# arm_v1.net
KiCad netlist of a schematic drawn in Altium Designer
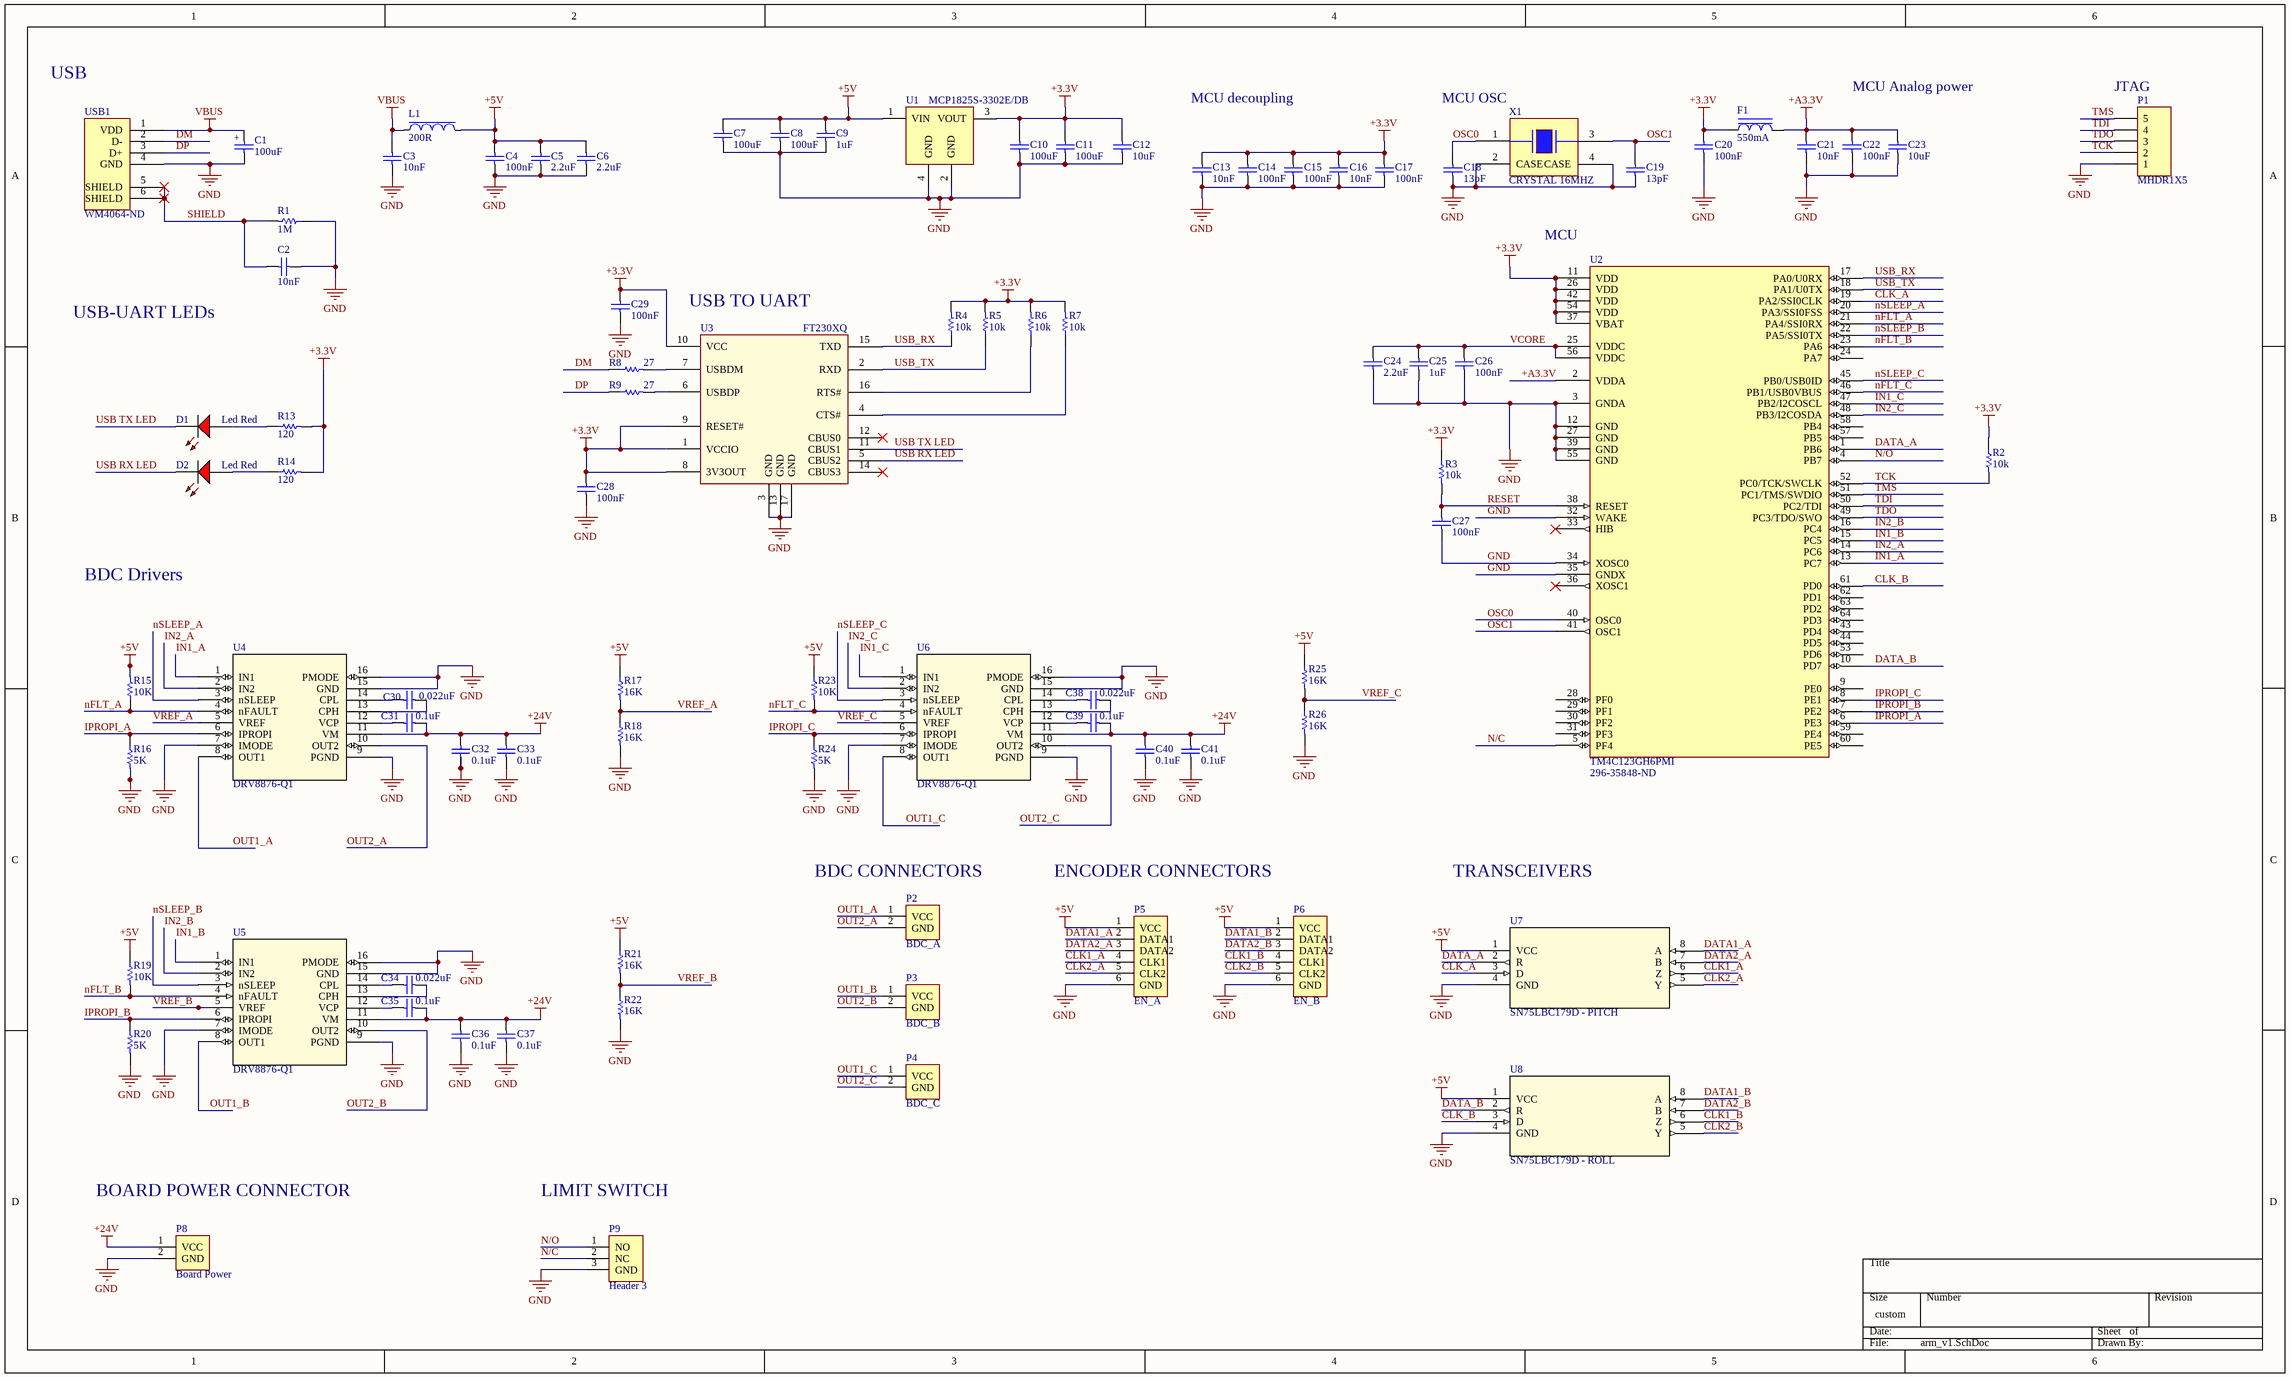
[diagram p0: arm_v1.SchDoc]

(export (version "E")
  (design (tool "Eeschema 10.0.6"))
  (components
    (comp (ref "C1")
      (value "100uF")
      (footprint "CapAlu6.3mmx12.5mm")
      (description "Capacitor 35v 100uF 6.3mm")
      (fields
        (field (name "MANUFACTURER") "Nichicon")
        (field (name "MANUFACTURER PART NUMBER") "UHV1V101MED")
      )
      (libsource (lib "Capacitors") (part "100uF_35v_6.3x12.5"))
    )
    (comp (ref "C2")
      (value "10nF")
      (footprint "CAP_1206")
      (description "CAP CER 10000PF 500V X7R 1206")
      (fields
        (field (name "MANUFACTURER") "Samsung Electro-Mechanics America, Inc")
        (field (name "MANUFACTURER PART NUMBER") "CL31B103KGFNNNE")
      )
      (libsource (lib "Capacitors") (part "10nF_500V_1206"))
    )
    (comp (ref "C3")
      (value "10nF")
      (footprint "CAP_0402_M")
      (description "CAP CER 10000PF 50V 10% X7R 0402")
      (fields
        (field (name "MANUFACTURER") "Kemet")
        (field (name "MANUFACTURER PART NUMBER") "C0402C103K5RACTU")
      )
      (libsource (lib "Capacitors") (part "10nF_50V_0402"))
    )
    (comp (ref "C4")
      (value "100nF")
      (footprint "CAP_0402_M")
      (description "CAP CER 100NF 50V 20% X5R 0402")
      (fields
        (field (name "MANUFACTURER") "TDK Corporation")
        (field (name "MANUFACTURER PART NUMBER") "C1005X5R1H104M050BB")
      )
      (libsource (lib "Capacitors") (part "100nF_50V_0402"))
    )
    (comp (ref "C5")
      (value "2.2uF")
      (footprint "CAP_0402_M")
      (description "CAP CER 2.2UF 10V 20% X5R 0402")
      (fields
        (field (name "MANUFACTURER") "Taiyo Yuden")
        (field (name "MANUFACTURER PART NUMBER") "LMK105BJ225MV-F")
      )
      (libsource (lib "Capacitors") (part "2.2uF_10V_0402"))
    )
    (comp (ref "C6")
      (value "2.2uF")
      (footprint "CAP_0402_M")
      (description "CAP CER 2.2UF 10V 20% X5R 0402")
      (fields
        (field (name "MANUFACTURER") "Taiyo Yuden")
        (field (name "MANUFACTURER PART NUMBER") "LMK105BJ225MV-F")
      )
      (libsource (lib "Capacitors") (part "2.2uF_10V_0402"))
    )
    (comp (ref "C7")
      (value "100uF")
      (footprint "CAP_1206")
      (description "CAP CER 100UF 6.3V X5R 1206")
      (fields
        (field (name "MANUFACTURER") "Murata Electronics North America")
        (field (name "MANUFACTURER PART NUMBER") "GRM31CR60J107ME39L")
      )
      (libsource (lib "Capacitors") (part "100uF_6.3v_1206_X5R"))
    )
    (comp (ref "C8")
      (value "100uF")
      (footprint "CAP_1206")
      (description "CAP CER 100UF 6.3V X5R 1206")
      (fields
        (field (name "MANUFACTURER") "Murata Electronics North America")
        (field (name "MANUFACTURER PART NUMBER") "GRM31CR60J107ME39L")
      )
      (libsource (lib "Capacitors") (part "100uF_6.3v_1206_X5R"))
    )
    (comp (ref "C9")
      (value "1uF")
      (footprint "CAP_0402_M")
      (description "CAP CER 1UF 25V 10% X5R 0402")
      (fields
        (field (name "MANUFACTURER") "TDK Corporation")
        (field (name "MANUFACTURER PART NUMBER") "C1005X5R1E105K050BC")
      )
      (libsource (lib "Capacitors") (part "1uF_25V_0402"))
    )
    (comp (ref "C10")
      (value "100uF")
      (footprint "CAP_1206")
      (description "CAP CER 100UF 6.3V X5R 1206")
      (fields
        (field (name "MANUFACTURER") "Murata Electronics North America")
        (field (name "MANUFACTURER PART NUMBER") "GRM31CR60J107ME39L")
      )
      (libsource (lib "Capacitors") (part "100uF_6.3v_1206_X5R"))
    )
    (comp (ref "C11")
      (value "100uF")
      (footprint "CAP_1206")
      (description "CAP CER 100UF 6.3V X5R 1206")
      (fields
        (field (name "MANUFACTURER") "Murata Electronics North America")
        (field (name "MANUFACTURER PART NUMBER") "GRM31CR60J107ME39L")
      )
      (libsource (lib "Capacitors") (part "100uF_6.3v_1206_X5R"))
    )
    (comp (ref "C12")
      (value "10uF")
      (footprint "CAP_0603")
      (description "CAP CER 10UF 10V 20% X5R 0603")
      (fields
        (field (name "MANUFACTURER") "Taiyo Yuden")
        (field (name "MANUFACTURER PART NUMBER") "LMK107BBJ106MAHT")
      )
      (libsource (lib "Capacitors") (part "10uF_10V_0603"))
    )
    (comp (ref "C13")
      (value "10nF")
      (footprint "CAP_0402_M")
      (description "CAP CER 10000PF 50V 10% X7R 0402")
      (fields
        (field (name "MANUFACTURER") "Kemet")
        (field (name "MANUFACTURER PART NUMBER") "C0402C103K5RACTU")
      )
      (libsource (lib "Capacitors") (part "10nF_50V_0402"))
    )
    (comp (ref "C14")
      (value "100nF")
      (footprint "CAP_0402_M")
      (description "CAP CER 100NF 50V 20% X5R 0402")
      (fields
        (field (name "MANUFACTURER") "TDK Corporation")
        (field (name "MANUFACTURER PART NUMBER") "C1005X5R1H104M050BB")
      )
      (libsource (lib "Capacitors") (part "100nF_50V_0402"))
    )
    (comp (ref "C15")
      (value "100nF")
      (footprint "CAP_0402_M")
      (description "CAP CER 100NF 50V 20% X5R 0402")
      (fields
        (field (name "MANUFACTURER") "TDK Corporation")
        (field (name "MANUFACTURER PART NUMBER") "C1005X5R1H104M050BB")
      )
      (libsource (lib "Capacitors") (part "100nF_50V_0402"))
    )
    (comp (ref "C16")
      (value "10nF")
      (footprint "CAP_0402_M")
      (description "CAP CER 10000PF 50V 10% X7R 0402")
      (fields
        (field (name "MANUFACTURER") "Kemet")
        (field (name "MANUFACTURER PART NUMBER") "C0402C103K5RACTU")
      )
      (libsource (lib "Capacitors") (part "10nF_50V_0402"))
    )
    (comp (ref "C17")
      (value "100nF")
      (footprint "CAP_0402_M")
      (description "CAP CER 100NF 50V 20% X5R 0402")
      (fields
        (field (name "MANUFACTURER") "TDK Corporation")
        (field (name "MANUFACTURER PART NUMBER") "C1005X5R1H104M050BB")
      )
      (libsource (lib "Capacitors") (part "100nF_50V_0402"))
    )
    (comp (ref "C18")
      (value "13pF")
      (footprint "CAP_0402_M")
      (description "CAP CER 13PF 50V 5% NP0 0402")
      (fields
        (field (name "MANUFACTURER") "Samsung Electro-Mechanics America, Inc")
        (field (name "MANUFACTURER PART NUMBER") "CL05C130JB5NNNC")
      )
      (libsource (lib "Capacitors") (part "13pF_50V_0402"))
    )
    (comp (ref "C19")
      (value "13pF")
      (footprint "CAP_0402_M")
      (description "CAP CER 13PF 50V 5% NP0 0402")
      (fields
        (field (name "MANUFACTURER") "Samsung Electro-Mechanics America, Inc")
        (field (name "MANUFACTURER PART NUMBER") "CL05C130JB5NNNC")
      )
      (libsource (lib "Capacitors") (part "13pF_50V_0402"))
    )
    (comp (ref "C20")
      (value "100nF")
      (footprint "CAP_0402_M")
      (description "CAP CER 100NF 50V 20% X5R 0402")
      (fields
        (field (name "MANUFACTURER") "TDK Corporation")
        (field (name "MANUFACTURER PART NUMBER") "C1005X5R1H104M050BB")
      )
      (libsource (lib "Capacitors") (part "100nF_50V_0402"))
    )
    (comp (ref "C21")
      (value "10nF")
      (footprint "CAP_0402_M")
      (description "CAP CER 10000PF 50V 10% X7R 0402")
      (fields
        (field (name "MANUFACTURER") "Kemet")
        (field (name "MANUFACTURER PART NUMBER") "C0402C103K5RACTU")
      )
      (libsource (lib "Capacitors") (part "10nF_50V_0402"))
    )
    (comp (ref "C22")
      (value "100nF")
      (footprint "CAP_0402_M")
      (description "CAP CER 100NF 50V 20% X5R 0402")
      (fields
        (field (name "MANUFACTURER") "TDK Corporation")
        (field (name "MANUFACTURER PART NUMBER") "C1005X5R1H104M050BB")
      )
      (libsource (lib "Capacitors") (part "100nF_50V_0402"))
    )
    (comp (ref "C23")
      (value "10uF")
      (footprint "CAP_0603")
      (description "CAP CER 10UF 10V 20% X5R 0603")
      (fields
        (field (name "MANUFACTURER") "Taiyo Yuden")
        (field (name "MANUFACTURER PART NUMBER") "LMK107BBJ106MAHT")
      )
      (libsource (lib "Capacitors") (part "10uF_10V_0603"))
    )
    (comp (ref "C24")
      (value "2.2uF")
      (footprint "CAP_0603")
      (description "CAP CER 2.2UF 35V 10% X5R 0603")
      (fields
        (field (name "MANUFACTURER") "Murata Electronics North America")
        (field (name "MANUFACTURER PART NUMBER") "GRM188R6YA225KA12D")
      )
      (libsource (lib "Capacitors") (part "2.2uF_35V_0603"))
    )
    (comp (ref "C25")
      (value "1uF")
      (footprint "CAP_0402_M")
      (description "CAP CER 1UF 25V 10% X5R 0402")
      (fields
        (field (name "MANUFACTURER") "TDK Corporation")
        (field (name "MANUFACTURER PART NUMBER") "C1005X5R1E105K050BC")
      )
      (libsource (lib "Capacitors") (part "1uF_25V_0402"))
    )
    (comp (ref "C26")
      (value "100nF")
      (footprint "CAP_0402_M")
      (description "CAP CER 100NF 50V 20% X5R 0402")
      (fields
        (field (name "MANUFACTURER") "TDK Corporation")
        (field (name "MANUFACTURER PART NUMBER") "C1005X5R1H104M050BB")
      )
      (libsource (lib "Capacitors") (part "100nF_50V_0402"))
    )
    (comp (ref "C27")
      (value "100nF")
      (footprint "CAP_0402_M")
      (description "CAP CER 100NF 50V 20% X5R 0402")
      (fields
        (field (name "MANUFACTURER") "TDK Corporation")
        (field (name "MANUFACTURER PART NUMBER") "C1005X5R1H104M050BB")
      )
      (libsource (lib "Capacitors") (part "100nF_50V_0402"))
    )
    (comp (ref "C28")
      (value "100nF")
      (footprint "CAP_0402_M")
      (description "CAP CER 100NF 50V 20% X5R 0402")
      (fields
        (field (name "MANUFACTURER") "TDK Corporation")
        (field (name "MANUFACTURER PART NUMBER") "C1005X5R1H104M050BB")
      )
      (libsource (lib "Capacitors") (part "100nF_50V_0402"))
    )
    (comp (ref "C29")
      (value "100nF")
      (footprint "CAP_0402_M")
      (description "CAP CER 100NF 50V 20% X5R 0402")
      (fields
        (field (name "MANUFACTURER") "TDK Corporation")
        (field (name "MANUFACTURER PART NUMBER") "C1005X5R1H104M050BB")
      )
      (libsource (lib "Capacitors") (part "100nF_50V_0402"))
    )
    (comp (ref "C30")
      (value "0.022uF")
      (footprint "CAP_0402_M")
      (description "CAP CER 100NF 50V 20% X5R 0402")
      (fields
        (field (name "MANUFACTURER") "TDK Corporation")
        (field (name "MANUFACTURER PART NUMBER") "C1005X5R1H104M050BB")
      )
      (libsource (lib "Capacitors") (part "100nF_50V_0402"))
    )
    (comp (ref "C31")
      (value "0.1uF")
      (footprint "CAP_0402_M")
      (description "CAP CER 100NF 50V 20% X5R 0402")
      (fields
        (field (name "MANUFACTURER") "TDK Corporation")
        (field (name "MANUFACTURER PART NUMBER") "C1005X5R1H104M050BB")
      )
      (libsource (lib "Capacitors") (part "100nF_50V_0402"))
    )
    (comp (ref "C32")
      (value "0.1uF")
      (footprint "CAP_0402_M")
      (description "CAP CER 100NF 50V 20% X5R 0402")
      (fields
        (field (name "MANUFACTURER") "TDK Corporation")
        (field (name "MANUFACTURER PART NUMBER") "C1005X5R1H104M050BB")
      )
      (libsource (lib "Capacitors") (part "100nF_50V_0402"))
    )
    (comp (ref "C33")
      (value "0.1uF")
      (footprint "CAP_0402_M")
      (description "CAP CER 100NF 50V 20% X5R 0402")
      (fields
        (field (name "MANUFACTURER") "TDK Corporation")
        (field (name "MANUFACTURER PART NUMBER") "C1005X5R1H104M050BB")
      )
      (libsource (lib "Capacitors") (part "100nF_50V_0402"))
    )
    (comp (ref "C34")
      (value "0.022uF")
      (footprint "CAP_0402_M")
      (description "CAP CER 100NF 50V 20% X5R 0402")
      (fields
        (field (name "MANUFACTURER") "TDK Corporation")
        (field (name "MANUFACTURER PART NUMBER") "C1005X5R1H104M050BB")
      )
      (libsource (lib "Capacitors") (part "100nF_50V_0402"))
    )
    (comp (ref "C35")
      (value "0.1uF")
      (footprint "CAP_0402_M")
      (description "CAP CER 100NF 50V 20% X5R 0402")
      (fields
        (field (name "MANUFACTURER") "TDK Corporation")
        (field (name "MANUFACTURER PART NUMBER") "C1005X5R1H104M050BB")
      )
      (libsource (lib "Capacitors") (part "100nF_50V_0402"))
    )
    (comp (ref "C36")
      (value "0.1uF")
      (footprint "CAP_0402_M")
      (description "CAP CER 100NF 50V 20% X5R 0402")
      (fields
        (field (name "MANUFACTURER") "TDK Corporation")
        (field (name "MANUFACTURER PART NUMBER") "C1005X5R1H104M050BB")
      )
      (libsource (lib "Capacitors") (part "100nF_50V_0402"))
    )
    (comp (ref "C37")
      (value "0.1uF")
      (footprint "CAP_0402_M")
      (description "CAP CER 100NF 50V 20% X5R 0402")
      (fields
        (field (name "MANUFACTURER") "TDK Corporation")
        (field (name "MANUFACTURER PART NUMBER") "C1005X5R1H104M050BB")
      )
      (libsource (lib "Capacitors") (part "100nF_50V_0402"))
    )
    (comp (ref "C38")
      (value "0.022uF")
      (footprint "CAP_0402_M")
      (description "CAP CER 100NF 50V 20% X5R 0402")
      (fields
        (field (name "MANUFACTURER") "TDK Corporation")
        (field (name "MANUFACTURER PART NUMBER") "C1005X5R1H104M050BB")
      )
      (libsource (lib "Capacitors") (part "100nF_50V_0402"))
    )
    (comp (ref "C39")
      (value "0.1uF")
      (footprint "CAP_0402_M")
      (description "CAP CER 100NF 50V 20% X5R 0402")
      (fields
        (field (name "MANUFACTURER") "TDK Corporation")
        (field (name "MANUFACTURER PART NUMBER") "C1005X5R1H104M050BB")
      )
      (libsource (lib "Capacitors") (part "100nF_50V_0402"))
    )
    (comp (ref "C40")
      (value "0.1uF")
      (footprint "CAP_0402_M")
      (description "CAP CER 100NF 50V 20% X5R 0402")
      (fields
        (field (name "MANUFACTURER") "TDK Corporation")
        (field (name "MANUFACTURER PART NUMBER") "C1005X5R1H104M050BB")
      )
      (libsource (lib "Capacitors") (part "100nF_50V_0402"))
    )
    (comp (ref "C41")
      (value "0.1uF")
      (footprint "CAP_0402_M")
      (description "CAP CER 100NF 50V 20% X5R 0402")
      (fields
        (field (name "MANUFACTURER") "TDK Corporation")
        (field (name "MANUFACTURER PART NUMBER") "C1005X5R1H104M050BB")
      )
      (libsource (lib "Capacitors") (part "100nF_50V_0402"))
    )
    (comp (ref "D1")
      (value "Led Red")
      (footprint "TOPLED 0805")
      (description "LED TOPLED 630NM SUP RED CLR SMD")
      (fields
        (field (name "MANUFACTURER") "OSRAM Opto Semiconductors Inc")
        (field (name "MANUFACTURER PART NUMBER") "LS M67K-H2L1-1-Z")
      )
      (libsource (lib "Diodes") (part "TOPLED 0803"))
    )
    (comp (ref "D2")
      (value "Led Red")
      (footprint "TOPLED 0805")
      (description "LED TOPLED 630NM SUP RED CLR SMD")
      (fields
        (field (name "MANUFACTURER") "OSRAM Opto Semiconductors Inc")
        (field (name "MANUFACTURER PART NUMBER") "LS M67K-H2L1-1-Z")
      )
      (libsource (lib "Diodes") (part "TOPLED 0803"))
    )
    (comp (ref "F1")
      (value "550mA")
      (footprint "RES_0402_M")
      (description "FERRITE CHIP 40 OHM 550MA 0402")
      (fields
        (field (name "MANUFACTURER") "TDK Corporation")
        (field (name "MANUFACTURER PART NUMBER") "MMZ1005Y400CT000")
      )
      (libsource (lib "Resistors") (part "40O_550mA_0402"))
    )
    (comp (ref "L1")
      (value "200R")
      (footprint "IND_0603")
      (description "FILTER CHIP 220 OHM 2A 0603")
      (fields
        (field (name "MANUFACTURER") "Murata Electronics North America")
        (field (name "MANUFACTURER PART NUMBER") "BLM18EG221SN1D")
      )
      (libsource (lib "Inductors") (part "Ferrite_200 ohms_2A"))
    )
    (comp (ref "P1")
      (value "MHDR1X5")
      (footprint "MHDR1X5")
      (description "Header, 5-Pin")
      (fields (field (name "PUBLISHER") "Altium Limited"))
      (libsource (lib "Miscellaneous Connectors") (part "MHDR1X5"))
    )
    (comp (ref "P2")
      (value "BDC_A")
      (footprint "HDR1X2")
      (description "Header, 2-Pin")
      (fields (field (name "PUBLISHER") "Altium Limited"))
      (libsource (lib "Miscellaneous Connectors") (part "Header 2"))
    )
    (comp (ref "P3")
      (value "BDC_B")
      (footprint "HDR1X2")
      (description "Header, 2-Pin")
      (fields (field (name "PUBLISHER") "Altium Limited"))
      (libsource (lib "Miscellaneous Connectors") (part "Header 2"))
    )
    (comp (ref "P4")
      (value "BDC_C")
      (footprint "HDR1X2")
      (description "Header, 2-Pin")
      (fields (field (name "PUBLISHER") "Altium Limited"))
      (libsource (lib "Miscellaneous Connectors") (part "Header 2"))
    )
    (comp (ref "P5")
      (value "EN_A")
      (footprint "HDR1X6")
      (description "Header, 6-Pin")
      (fields (field (name "PUBLISHER") "Altium Limited"))
      (libsource (lib "Miscellaneous Connectors") (part "Header 6"))
    )
    (comp (ref "P6")
      (value "EN_B")
      (footprint "HDR1X6")
      (description "Header, 6-Pin")
      (fields (field (name "PUBLISHER") "Altium Limited"))
      (libsource (lib "Miscellaneous Connectors") (part "Header 6"))
    )
    (comp (ref "P8")
      (value "Board Power")
      (footprint "HDR1X2H")
      (description "Header, 2-Pin, Right Angle")
      (fields (field (name "PUBLISHER") "Altium Limited"))
      (libsource (lib "Miscellaneous Connectors") (part "Header 2H"))
    )
    (comp (ref "P9")
      (value "Header 3")
      (footprint "HDR1X3")
      (description "Header, 3-Pin")
      (fields (field (name "PUBLISHER") "Altium Limited"))
      (libsource (lib "Miscellaneous Connectors") (part "Header 3"))
    )
    (comp (ref "R1")
      (value "1M")
      (footprint "RES_1206")
      (description "RES SMD 1M OHM 5% 1/4W 1206")
      (fields
        (field (name "MANUFACTURER") "Panasonic Electronic Components")
        (field (name "MANUFACTURER PART NUMBER") "ERJ-8GEYJ105V")
      )
      (libsource (lib "Resistors") (part "1M_5%_1206"))
    )
    (comp (ref "R2")
      (value "10k")
      (footprint "RES_0402_M")
      (description "RES SMD 10K OHM 1% 1/10W 0402")
      (fields
        (field (name "MANUFACTURER") "Panasonic Electronic Components")
        (field (name "MANUFACTURER PART NUMBER") "ERJ-2RKF1002X")
      )
      (libsource (lib "Resistors") (part "10k_1%_0402"))
    )
    (comp (ref "R3")
      (value "10k")
      (footprint "RES_0402_M")
      (description "RES SMD 10K OHM 1% 1/10W 0402")
      (fields
        (field (name "MANUFACTURER") "Panasonic Electronic Components")
        (field (name "MANUFACTURER PART NUMBER") "ERJ-2RKF1002X")
      )
      (libsource (lib "Resistors") (part "10k_1%_0402"))
    )
    (comp (ref "R4")
      (value "10k")
      (footprint "RES_0402_M")
      (description "RES SMD 10K OHM 1% 1/10W 0402")
      (fields
        (field (name "MANUFACTURER") "Panasonic Electronic Components")
        (field (name "MANUFACTURER PART NUMBER") "ERJ-2RKF1002X")
      )
      (libsource (lib "Resistors") (part "10k_1%_0402"))
    )
    (comp (ref "R5")
      (value "10k")
      (footprint "RES_0402_M")
      (description "RES SMD 10K OHM 1% 1/10W 0402")
      (fields
        (field (name "MANUFACTURER") "Panasonic Electronic Components")
        (field (name "MANUFACTURER PART NUMBER") "ERJ-2RKF1002X")
      )
      (libsource (lib "Resistors") (part "10k_1%_0402"))
    )
    (comp (ref "R6")
      (value "10k")
      (footprint "RES_0402_M")
      (description "RES SMD 10K OHM 1% 1/10W 0402")
      (fields
        (field (name "MANUFACTURER") "Panasonic Electronic Components")
        (field (name "MANUFACTURER PART NUMBER") "ERJ-2RKF1002X")
      )
      (libsource (lib "Resistors") (part "10k_1%_0402"))
    )
    (comp (ref "R7")
      (value "10k")
      (footprint "RES_0402_M")
      (description "RES SMD 10K OHM 1% 1/10W 0402")
      (fields
        (field (name "MANUFACTURER") "Panasonic Electronic Components")
        (field (name "MANUFACTURER PART NUMBER") "ERJ-2RKF1002X")
      )
      (libsource (lib "Resistors") (part "10k_1%_0402"))
    )
    (comp (ref "R8")
      (value "27")
      (footprint "RES_0402_M")
      (description "RES SMD 27 OHM 1% 1/10W 0402")
      (fields
        (field (name "MANUFACTURER") "Panasonic Electronic Components")
        (field (name "MANUFACTURER PART NUMBER") "ERJ-2RKF27R0X")
      )
      (libsource (lib "Resistors") (part "27_1%_0402"))
    )
    (comp (ref "R9")
      (value "27")
      (footprint "RES_0402_M")
      (description "RES SMD 27 OHM 1% 1/10W 0402")
      (fields
        (field (name "MANUFACTURER") "Panasonic Electronic Components")
        (field (name "MANUFACTURER PART NUMBER") "ERJ-2RKF27R0X")
      )
      (libsource (lib "Resistors") (part "27_1%_0402"))
    )
    (comp (ref "R13")
      (value "120")
      (footprint "RES_0402_M")
      (description "RES SMD 120 OHM 1% 1/10W 0402")
      (fields
        (field (name "MANUFACTURER") "Panasonic Electronic Components")
        (field (name "MANUFACTURER PART NUMBER") "ERJ-2RKF1200X")
      )
      (libsource (lib "Resistors") (part "120_1%_0402"))
    )
    (comp (ref "R14")
      (value "120")
      (footprint "RES_0402_M")
      (description "RES SMD 120 OHM 1% 1/10W 0402")
      (fields
        (field (name "MANUFACTURER") "Panasonic Electronic Components")
        (field (name "MANUFACTURER PART NUMBER") "ERJ-2RKF1200X")
      )
      (libsource (lib "Resistors") (part "120_1%_0402"))
    )
    (comp (ref "R15")
      (value "10K")
      (footprint "RES_0402_M")
      (description "RES SMD 0 OHM JUMPER 1/16W 0402")
      (fields
        (field (name "MANUFACTURER") "Yageo")
        (field (name "MANUFACTURER PART NUMBER") "RC0402FR-070RL")
      )
      (libsource (lib "Resistors") (part "0_0402"))
    )
    (comp (ref "R16")
      (value "5K")
      (footprint "RES_0402_M")
      (description "RES SMD 0 OHM JUMPER 1/16W 0402")
      (fields
        (field (name "MANUFACTURER") "Yageo")
        (field (name "MANUFACTURER PART NUMBER") "RC0402FR-070RL")
      )
      (libsource (lib "Resistors") (part "0_0402"))
    )
    (comp (ref "R17")
      (value "16K")
      (footprint "RES_0402_M")
      (description "RES SMD 0 OHM JUMPER 1/16W 0402")
      (fields
        (field (name "MANUFACTURER") "Yageo")
        (field (name "MANUFACTURER PART NUMBER") "RC0402FR-070RL")
      )
      (libsource (lib "Resistors") (part "0_0402"))
    )
    (comp (ref "R18")
      (value "16K")
      (footprint "RES_0402_M")
      (description "RES SMD 0 OHM JUMPER 1/16W 0402")
      (fields
        (field (name "MANUFACTURER") "Yageo")
        (field (name "MANUFACTURER PART NUMBER") "RC0402FR-070RL")
      )
      (libsource (lib "Resistors") (part "0_0402"))
    )
    (comp (ref "R19")
      (value "10K")
      (footprint "RES_0402_M")
      (description "RES SMD 0 OHM JUMPER 1/16W 0402")
      (fields
        (field (name "MANUFACTURER") "Yageo")
        (field (name "MANUFACTURER PART NUMBER") "RC0402FR-070RL")
      )
      (libsource (lib "Resistors") (part "0_0402"))
    )
    (comp (ref "R20")
      (value "5K")
      (footprint "RES_0402_M")
      (description "RES SMD 0 OHM JUMPER 1/16W 0402")
      (fields
        (field (name "MANUFACTURER") "Yageo")
        (field (name "MANUFACTURER PART NUMBER") "RC0402FR-070RL")
      )
      (libsource (lib "Resistors") (part "0_0402"))
    )
    (comp (ref "R21")
      (value "16K")
      (footprint "RES_0402_M")
      (description "RES SMD 0 OHM JUMPER 1/16W 0402")
      (fields
        (field (name "MANUFACTURER") "Yageo")
        (field (name "MANUFACTURER PART NUMBER") "RC0402FR-070RL")
      )
      (libsource (lib "Resistors") (part "0_0402"))
    )
    (comp (ref "R22")
      (value "16K")
      (footprint "RES_0402_M")
      (description "RES SMD 0 OHM JUMPER 1/16W 0402")
      (fields
        (field (name "MANUFACTURER") "Yageo")
        (field (name "MANUFACTURER PART NUMBER") "RC0402FR-070RL")
      )
      (libsource (lib "Resistors") (part "0_0402"))
    )
    (comp (ref "R23")
      (value "10K")
      (footprint "RES_0402_M")
      (description "RES SMD 0 OHM JUMPER 1/16W 0402")
      (fields
        (field (name "MANUFACTURER") "Yageo")
        (field (name "MANUFACTURER PART NUMBER") "RC0402FR-070RL")
      )
      (libsource (lib "Resistors") (part "0_0402"))
    )
    (comp (ref "R24")
      (value "5K")
      (footprint "RES_0402_M")
      (description "RES SMD 0 OHM JUMPER 1/16W 0402")
      (fields
        (field (name "MANUFACTURER") "Yageo")
        (field (name "MANUFACTURER PART NUMBER") "RC0402FR-070RL")
      )
      (libsource (lib "Resistors") (part "0_0402"))
    )
    (comp (ref "R25")
      (value "16K")
      (footprint "RES_0402_M")
      (description "RES SMD 0 OHM JUMPER 1/16W 0402")
      (fields
        (field (name "MANUFACTURER") "Yageo")
        (field (name "MANUFACTURER PART NUMBER") "RC0402FR-070RL")
      )
      (libsource (lib "Resistors") (part "0_0402"))
    )
    (comp (ref "R26")
      (value "16K")
      (footprint "RES_0402_M")
      (description "RES SMD 0 OHM JUMPER 1/16W 0402")
      (fields
        (field (name "MANUFACTURER") "Yageo")
        (field (name "MANUFACTURER PART NUMBER") "RC0402FR-070RL")
      )
      (libsource (lib "Resistors") (part "0_0402"))
    )
    (comp (ref "U1")
      (value "MCP1825S-3302E/DB")
      (footprint "SOT230P700X180-4N")
      (description "500 mA, Low Voltage, Low Quiescent Current LDO Regulator")
      (fields (field (name "MANUFACTURER") "Microchip Technology"))
      (libsource (lib "ICs") (part "MCP1825S-3302E/DB"))
    )
    (comp (ref "U2")
      (value "TM4C123GH6PMI")
      (footprint "TSQFP50P1200X1200X120-64N")
      (description "Tiva TM4C123GH6PM Microcontroller ARM Cortex 80 MHz FPU")
      (fields (field (name "SUPPLIER PART NUMBER 1") "296-35848-ND"))
      (libsource (lib "ICs") (part "TM4C123GH6PMI"))
    )
    (comp (ref "U3")
      (value "FT230XQ")
      (footprint "QFN65P400X400X80_HS-17N")
      (description "IC USB SERIAL BASIC UART 16QFN")
      (fields
        (field (name "MANUFACTURER") "FTDI, Future Technology Devices International Ltd")
        (field (name "MANUFACTURER PART NUMBER") "FT230XQ-R")
      )
      (libsource (lib "ICs") (part "FT230XQ-R"))
    )
    (comp (ref "U4")
      (value "DRV8876-Q1")
      (footprint "SOIC_PWPRQ1_TEX")
      (description "No Description Available")
      (fields
        (field (name "MANUFACTURER_PART_NUMBER") "DRV8876QPWPRQ1")
        (field (name "COPYRIGHT") "Copyright (C) 2018 Accelerated Designs. All rights reserved")
      )
      (libsource (lib "DRV8876") (part "DRV8876QPWPRQ1"))
    )
    (comp (ref "U5")
      (value "DRV8876-Q1")
      (footprint "SOIC_PWPRQ1_TEX")
      (description "No Description Available")
      (fields
        (field (name "MANUFACTURER_PART_NUMBER") "DRV8876QPWPRQ1")
        (field (name "COPYRIGHT") "Copyright (C) 2018 Accelerated Designs. All rights reserved")
      )
      (libsource (lib "DRV8876") (part "DRV8876QPWPRQ1"))
    )
    (comp (ref "U6")
      (value "DRV8876-Q1")
      (footprint "SOIC_PWPRQ1_TEX")
      (description "No Description Available")
      (fields
        (field (name "MANUFACTURER_PART_NUMBER") "DRV8876QPWPRQ1")
        (field (name "COPYRIGHT") "Copyright (C) 2018 Accelerated Designs. All rights reserved")
      )
      (libsource (lib "DRV8876") (part "DRV8876QPWPRQ1"))
    )
    (comp (ref "U7")
      (value "SN75LBC179D - PITCH")
      (footprint "D8")
      (description "Low-Power Differential Line Driver And Receiver Pair")
      (fields
        (field (name "MANUFACTURER") "Texas Instruments")
        (field (name "GENERIC_PART_NUMBER") "SN75LBC179")
        (field (name "COPYRIGHT") "Copyright (C) 2018 Accelerated Designs. All rights reserved")
      )
      (libsource (lib "SN75LBC179DR") (part "SN75LBC179D"))
    )
    (comp (ref "U8")
      (value "SN75LBC179D - ROLL")
      (footprint "D8")
      (description "Low-Power Differential Line Driver And Receiver Pair")
      (fields
        (field (name "MANUFACTURER") "Texas Instruments")
        (field (name "GENERIC_PART_NUMBER") "SN75LBC179")
        (field (name "COPYRIGHT") "Copyright (C) 2018 Accelerated Designs. All rights reserved")
      )
      (libsource (lib "SN75LBC179DR") (part "SN75LBC179D"))
    )
    (comp (ref "USB1")
      (value "USB type-B jack")
      (footprint "USB2.5-2H4E")
      (fields (field (name "SUPPLIER PART NUMBER 1") "WM4064-ND"))
      (libsource (lib "Connectors") (part "MOLEX 0670688010"))
    )
    (comp (ref "X1")
      (value "CRYSTAL 16MHZ")
      (footprint "CRYSTAL_3.2x2.5")
      (description "CRYSTAL 16MHZ 20PF SMD")
      (fields
        (field (name "MANUFACTURER") "CTS-Frequency Controls")
        (field (name "MANUFACTURER PART NUMBER") "403C35E16M00000")
      )
      (libsource (lib "ICs") (part "403C35E16M00000"))
    )
  )
  (nets
    (net (code "1") (name "+3.3V") (class "Default")
      (node (ref "C10") (pin "1") (pinfunction "1_1") (pintype "passive"))
      (node (ref "C11") (pin "1") (pinfunction "1_1") (pintype "passive"))
      (node (ref "C12") (pin "1") (pinfunction "1_1") (pintype "passive"))
      (node (ref "C13") (pin "2") (pinfunction "2_2") (pintype "passive"))
      (node (ref "C14") (pin "2") (pinfunction "2_2") (pintype "passive"))
      (node (ref "C15") (pin "2") (pinfunction "2_2") (pintype "passive"))
      (node (ref "C16") (pin "2") (pinfunction "2_2") (pintype "passive"))
      (node (ref "C17") (pin "2") (pinfunction "2_2") (pintype "passive"))
      (node (ref "C20") (pin "2") (pinfunction "2_2") (pintype "passive"))
      (node (ref "C28") (pin "2") (pinfunction "2_2") (pintype "passive"))
      (node (ref "C29") (pin "2") (pinfunction "2_2") (pintype "passive"))
      (node (ref "F1") (pin "1") (pinfunction "1_1") (pintype "passive"))
      (node (ref "R13") (pin "2") (pinfunction "2_2") (pintype "passive"))
      (node (ref "R14") (pin "2") (pinfunction "2_2") (pintype "passive"))
      (node (ref "R2") (pin "1") (pinfunction "1_1") (pintype "passive"))
      (node (ref "R3") (pin "1") (pinfunction "1_1") (pintype "passive"))
      (node (ref "R4") (pin "2") (pinfunction "2_2") (pintype "passive"))
      (node (ref "R5") (pin "2") (pinfunction "2_2") (pintype "passive"))
      (node (ref "R6") (pin "2") (pinfunction "2_2") (pintype "passive"))
      (node (ref "R7") (pin "2") (pinfunction "2_2") (pintype "passive"))
      (node (ref "U1") (pin "3") (pinfunction "VOUT_3") (pintype "power_in"))
      (node (ref "U2") (pin "11") (pinfunction "VDD_11") (pintype "power_in"))
      (node (ref "U2") (pin "26") (pinfunction "VDD_26") (pintype "power_in"))
      (node (ref "U2") (pin "37") (pinfunction "VBAT_37") (pintype "power_in"))
      (node (ref "U2") (pin "42") (pinfunction "VDD_42") (pintype "power_in"))
      (node (ref "U2") (pin "54") (pinfunction "VDD_54") (pintype "power_in"))
      (node (ref "U3") (pin "1") (pinfunction "VCCIO_1") (pintype "passive"))
      (node (ref "U3") (pin "10") (pinfunction "VCC_10") (pintype "passive"))
      (node (ref "U3") (pin "8") (pinfunction "3V3OUT_8") (pintype "passive"))
      (node (ref "U3") (pin "9") (pinfunction "RESET#_9") (pintype "passive"))
    )
    (net (code "2") (name "+5V") (class "Default")
      (node (ref "C4") (pin "2") (pinfunction "2_2") (pintype "passive"))
      (node (ref "C5") (pin "2") (pinfunction "2_2") (pintype "passive"))
      (node (ref "C6") (pin "2") (pinfunction "2_2") (pintype "passive"))
      (node (ref "C7") (pin "1") (pinfunction "1_1") (pintype "passive"))
      (node (ref "C8") (pin "1") (pinfunction "1_1") (pintype "passive"))
      (node (ref "C9") (pin "2") (pinfunction "2_2") (pintype "passive"))
      (node (ref "L1") (pin "2") (pinfunction "2_2") (pintype "passive"))
      (node (ref "P5") (pin "1") (pinfunction "VCC_1") (pintype "passive"))
      (node (ref "P6") (pin "1") (pinfunction "VCC_1") (pintype "passive"))
      (node (ref "R15") (pin "2") (pinfunction "2_2") (pintype "passive"))
      (node (ref "R17") (pin "1") (pinfunction "1_1") (pintype "passive"))
      (node (ref "R19") (pin "1") (pinfunction "1_1") (pintype "passive"))
      (node (ref "R21") (pin "1") (pinfunction "1_1") (pintype "passive"))
      (node (ref "R23") (pin "1") (pinfunction "1_1") (pintype "passive"))
      (node (ref "R25") (pin "1") (pinfunction "1_1") (pintype "passive"))
      (node (ref "U1") (pin "1") (pinfunction "VIN_1") (pintype "power_in"))
      (node (ref "U7") (pin "1") (pinfunction "VCC_1") (pintype "power_in"))
      (node (ref "U8") (pin "1") (pinfunction "VCC_1") (pintype "power_in"))
    )
    (net (code "3") (name "+24V") (class "Default")
      (node (ref "C31") (pin "2") (pinfunction "2_2") (pintype "passive"))
      (node (ref "C32") (pin "2") (pinfunction "2_2") (pintype "passive"))
      (node (ref "C33") (pin "2") (pinfunction "2_2") (pintype "passive"))
      (node (ref "C35") (pin "2") (pinfunction "2_2") (pintype "passive"))
      (node (ref "C36") (pin "2") (pinfunction "2_2") (pintype "passive"))
      (node (ref "C37") (pin "2") (pinfunction "2_2") (pintype "passive"))
      (node (ref "C39") (pin "2") (pinfunction "2_2") (pintype "passive"))
      (node (ref "C40") (pin "2") (pinfunction "2_2") (pintype "passive"))
      (node (ref "C41") (pin "2") (pinfunction "2_2") (pintype "passive"))
      (node (ref "P8") (pin "1") (pinfunction "VCC_1") (pintype "passive"))
      (node (ref "U4") (pin "11") (pinfunction "VM_11") (pintype "passive"))
      (node (ref "U5") (pin "11") (pinfunction "VM_11") (pintype "passive"))
      (node (ref "U6") (pin "11") (pinfunction "VM_11") (pintype "passive"))
    )
    (net (code "4") (name "+A3.3V") (class "Default")
      (node (ref "C21") (pin "2") (pinfunction "2_2") (pintype "passive"))
      (node (ref "C22") (pin "2") (pinfunction "2_2") (pintype "passive"))
      (node (ref "C23") (pin "2") (pinfunction "2_2") (pintype "passive"))
      (node (ref "F1") (pin "2") (pinfunction "2_2") (pintype "passive"))
      (node (ref "U2") (pin "2") (pinfunction "VDDA_2") (pintype "power_in"))
    )
    (net (code "5") (name "/CLK1_A") (class "Default")
      (node (ref "P5") (pin "4") (pinfunction "CLK1_4") (pintype "passive"))
      (node (ref "U7") (pin "6") (pinfunction "Z_6") (pintype "output"))
    )
    (net (code "6") (name "/CLK1_B") (class "Default")
      (node (ref "P6") (pin "4") (pinfunction "CLK1_4") (pintype "passive"))
      (node (ref "U8") (pin "6") (pinfunction "Z_6") (pintype "output"))
    )
    (net (code "7") (name "/CLK2_A") (class "Default")
      (node (ref "P5") (pin "5") (pinfunction "CLK2_5") (pintype "passive"))
      (node (ref "U7") (pin "5") (pinfunction "Y_5") (pintype "output"))
    )
    (net (code "8") (name "/CLK2_B") (class "Default")
      (node (ref "P6") (pin "5") (pinfunction "CLK2_5") (pintype "passive"))
      (node (ref "U8") (pin "5") (pinfunction "Y_5") (pintype "output"))
    )
    (net (code "9") (name "/CLK_A") (class "Default")
      (node (ref "U2") (pin "19") (pinfunction "PA2/SSI0CLK_19") (pintype "bidirectional"))
      (node (ref "U7") (pin "3") (pinfunction "D_3") (pintype "input"))
    )
    (net (code "10") (name "/CLK_B") (class "Default")
      (node (ref "U2") (pin "61") (pinfunction "PD0_61") (pintype "bidirectional"))
      (node (ref "U8") (pin "3") (pinfunction "D_3") (pintype "input"))
    )
    (net (code "11") (name "/DATA1_A") (class "Default")
      (node (ref "P5") (pin "2") (pinfunction "DATA1_2") (pintype "passive"))
      (node (ref "U7") (pin "8") (pinfunction "A_8") (pintype "input"))
    )
    (net (code "12") (name "/DATA1_B") (class "Default")
      (node (ref "P6") (pin "2") (pinfunction "DATA1_2") (pintype "passive"))
      (node (ref "U8") (pin "8") (pinfunction "A_8") (pintype "input"))
    )
    (net (code "13") (name "/DATA2_A") (class "Default")
      (node (ref "P5") (pin "3") (pinfunction "DATA2_3") (pintype "passive"))
      (node (ref "U7") (pin "7") (pinfunction "B_7") (pintype "input"))
    )
    (net (code "14") (name "/DATA2_B") (class "Default")
      (node (ref "P6") (pin "3") (pinfunction "DATA2_3") (pintype "passive"))
      (node (ref "U8") (pin "7") (pinfunction "B_7") (pintype "input"))
    )
    (net (code "15") (name "/DATA_A") (class "Default")
      (node (ref "U2") (pin "1") (pinfunction "PB6_1") (pintype "bidirectional"))
      (node (ref "U7") (pin "2") (pinfunction "R_2") (pintype "output"))
    )
    (net (code "16") (name "/DATA_B") (class "Default")
      (node (ref "U2") (pin "10") (pinfunction "PD7_10") (pintype "bidirectional"))
      (node (ref "U8") (pin "2") (pinfunction "R_2") (pintype "output"))
    )
    (net (code "17") (name "/DM") (class "Default")
      (node (ref "R8") (pin "1") (pinfunction "1_1") (pintype "passive"))
      (node (ref "USB1") (pin "2") (pinfunction "D-_2") (pintype "passive"))
    )
    (net (code "18") (name "/DP") (class "Default")
      (node (ref "R9") (pin "1") (pinfunction "1_1") (pintype "passive"))
      (node (ref "USB1") (pin "3") (pinfunction "D+_3") (pintype "passive"))
    )
    (net (code "19") (name "/IN1_A") (class "Default")
      (node (ref "U2") (pin "13") (pinfunction "PC7_13") (pintype "bidirectional"))
      (node (ref "U4") (pin "1") (pinfunction "IN1_1") (pintype "bidirectional"))
    )
    (net (code "20") (name "/IN1_B") (class "Default")
      (node (ref "U2") (pin "15") (pinfunction "PC5_15") (pintype "bidirectional"))
      (node (ref "U5") (pin "1") (pinfunction "IN1_1") (pintype "bidirectional"))
    )
    (net (code "21") (name "/IN1_C") (class "Default")
      (node (ref "U2") (pin "47") (pinfunction "PB2/I2COSCL_47") (pintype "bidirectional"))
      (node (ref "U6") (pin "1") (pinfunction "IN1_1") (pintype "bidirectional"))
    )
    (net (code "22") (name "/IN2_A") (class "Default")
      (node (ref "U2") (pin "14") (pinfunction "PC6_14") (pintype "bidirectional"))
      (node (ref "U4") (pin "2") (pinfunction "IN2_2") (pintype "bidirectional"))
    )
    (net (code "23") (name "/IN2_B") (class "Default")
      (node (ref "U2") (pin "16") (pinfunction "PC4_16") (pintype "bidirectional"))
      (node (ref "U5") (pin "2") (pinfunction "IN2_2") (pintype "bidirectional"))
    )
    (net (code "24") (name "/IN2_C") (class "Default")
      (node (ref "U2") (pin "48") (pinfunction "PB3/I2COSDA_48") (pintype "bidirectional"))
      (node (ref "U6") (pin "2") (pinfunction "IN2_2") (pintype "bidirectional"))
    )
    (net (code "25") (name "/IPROPI_A") (class "Default")
      (node (ref "R16") (pin "1") (pinfunction "1_1") (pintype "passive"))
      (node (ref "U2") (pin "6") (pinfunction "PE3_6") (pintype "bidirectional"))
      (node (ref "U4") (pin "6") (pinfunction "IPROPI_6") (pintype "bidirectional"))
    )
    (net (code "26") (name "/IPROPI_B") (class "Default")
      (node (ref "R20") (pin "1") (pinfunction "1_1") (pintype "passive"))
      (node (ref "U2") (pin "7") (pinfunction "PE2_7") (pintype "bidirectional"))
      (node (ref "U5") (pin "6") (pinfunction "IPROPI_6") (pintype "bidirectional"))
    )
    (net (code "27") (name "/IPROPI_C") (class "Default")
      (node (ref "R24") (pin "1") (pinfunction "1_1") (pintype "passive"))
      (node (ref "U2") (pin "8") (pinfunction "PE1_8") (pintype "bidirectional"))
      (node (ref "U6") (pin "6") (pinfunction "IPROPI_6") (pintype "bidirectional"))
    )
    (net (code "28") (name "/N{slash}C") (class "Default")
      (node (ref "P9") (pin "2") (pinfunction "NC_2") (pintype "passive"))
      (node (ref "U2") (pin "5") (pinfunction "PF4_5") (pintype "bidirectional"))
    )
    (net (code "29") (name "/N{slash}O") (class "Default")
      (node (ref "P9") (pin "1") (pinfunction "NO_1") (pintype "passive"))
      (node (ref "U2") (pin "4") (pinfunction "PB7_4") (pintype "bidirectional"))
    )
    (net (code "30") (name "/OSC0") (class "Default")
      (node (ref "C18") (pin "2") (pinfunction "2_2") (pintype "passive"))
      (node (ref "U2") (pin "40") (pinfunction "OSC0_40") (pintype "input"))
      (node (ref "X1") (pin "1") (pintype "passive"))
    )
    (net (code "31") (name "/OSC1") (class "Default")
      (node (ref "C19") (pin "2") (pinfunction "2_2") (pintype "passive"))
      (node (ref "U2") (pin "41") (pinfunction "OSC1_41") (pintype "output"))
      (node (ref "X1") (pin "3") (pintype "passive"))
    )
    (net (code "32") (name "/OUT1_A") (class "Default")
      (node (ref "P2") (pin "1") (pinfunction "VCC_1") (pintype "passive"))
      (node (ref "U4") (pin "8") (pinfunction "OUT1_8") (pintype "bidirectional"))
    )
    (net (code "33") (name "/OUT1_B") (class "Default")
      (node (ref "P3") (pin "1") (pinfunction "VCC_1") (pintype "passive"))
      (node (ref "U5") (pin "8") (pinfunction "OUT1_8") (pintype "bidirectional"))
    )
    (net (code "34") (name "/OUT1_C") (class "Default")
      (node (ref "P4") (pin "1") (pinfunction "VCC_1") (pintype "passive"))
      (node (ref "U6") (pin "8") (pinfunction "OUT1_8") (pintype "bidirectional"))
    )
    (net (code "35") (name "/OUT2_A") (class "Default")
      (node (ref "P2") (pin "2") (pinfunction "GND_2") (pintype "passive"))
      (node (ref "U4") (pin "10") (pinfunction "OUT2_10") (pintype "bidirectional"))
    )
    (net (code "36") (name "/OUT2_B") (class "Default")
      (node (ref "P3") (pin "2") (pinfunction "GND_2") (pintype "passive"))
      (node (ref "U5") (pin "10") (pinfunction "OUT2_10") (pintype "bidirectional"))
    )
    (net (code "37") (name "/OUT2_C") (class "Default")
      (node (ref "P4") (pin "2") (pinfunction "GND_2") (pintype "passive"))
      (node (ref "U6") (pin "10") (pinfunction "OUT2_10") (pintype "bidirectional"))
    )
    (net (code "38") (name "/RESET") (class "Default")
      (node (ref "C27") (pin "2") (pinfunction "2_2") (pintype "passive"))
      (node (ref "R3") (pin "2") (pinfunction "2_2") (pintype "passive"))
      (node (ref "U2") (pin "38") (pinfunction "RESET_38") (pintype "input"))
    )
    (net (code "39") (name "/SHIELD") (class "Default")
      (node (ref "C2") (pin "2") (pinfunction "2_2") (pintype "passive"))
      (node (ref "R1") (pin "2") (pinfunction "2_2") (pintype "passive"))
      (node (ref "USB1") (pin "5") (pinfunction "SHIELD_5") (pintype "passive"))
      (node (ref "USB1") (pin "6") (pinfunction "SHIELD_6") (pintype "passive"))
    )
    (net (code "40") (name "/TCK") (class "Default")
      (node (ref "P1") (pin "2") (pinfunction "2_2") (pintype "passive"))
      (node (ref "R2") (pin "2") (pinfunction "2_2") (pintype "passive"))
      (node (ref "U2") (pin "52") (pinfunction "PC0/TCK/SWCLK_52") (pintype "bidirectional"))
    )
    (net (code "41") (name "/TDI") (class "Default")
      (node (ref "P1") (pin "4") (pinfunction "4_4") (pintype "passive"))
      (node (ref "U2") (pin "50") (pinfunction "PC2/TDI_50") (pintype "bidirectional"))
    )
    (net (code "42") (name "/TDO") (class "Default")
      (node (ref "P1") (pin "3") (pinfunction "3_3") (pintype "passive"))
      (node (ref "U2") (pin "49") (pinfunction "PC3/TDO/SWO_49") (pintype "bidirectional"))
    )
    (net (code "43") (name "/TMS") (class "Default")
      (node (ref "P1") (pin "5") (pinfunction "5_5") (pintype "passive"))
      (node (ref "U2") (pin "51") (pinfunction "PC1/TMS/SWDIO_51") (pintype "bidirectional"))
    )
    (net (code "44") (name "/USB RX LED") (class "Default")
      (node (ref "D2") (pin "2") (pinfunction "K_2") (pintype "passive"))
      (node (ref "U3") (pin "5") (pinfunction "CBUS2_5") (pintype "passive"))
    )
    (net (code "45") (name "/USB TX LED") (class "Default")
      (node (ref "D1") (pin "2") (pinfunction "K_2") (pintype "passive"))
      (node (ref "U3") (pin "11") (pinfunction "CBUS1_11") (pintype "passive"))
    )
    (net (code "46") (name "/USB_RX") (class "Default")
      (node (ref "R4") (pin "1") (pinfunction "1_1") (pintype "passive"))
      (node (ref "U2") (pin "17") (pinfunction "PA0/U0RX_17") (pintype "bidirectional"))
      (node (ref "U3") (pin "15") (pinfunction "TXD_15") (pintype "passive"))
    )
    (net (code "47") (name "/USB_TX") (class "Default")
      (node (ref "R5") (pin "1") (pinfunction "1_1") (pintype "passive"))
      (node (ref "U2") (pin "18") (pinfunction "PA1/U0TX_18") (pintype "bidirectional"))
      (node (ref "U3") (pin "2") (pinfunction "RXD_2") (pintype "passive"))
    )
    (net (code "48") (name "/VCORE") (class "Default")
      (node (ref "C24") (pin "2") (pinfunction "2_2") (pintype "passive"))
      (node (ref "C25") (pin "2") (pinfunction "2_2") (pintype "passive"))
      (node (ref "C26") (pin "2") (pinfunction "2_2") (pintype "passive"))
      (node (ref "U2") (pin "25") (pinfunction "VDDC_25") (pintype "power_in"))
      (node (ref "U2") (pin "56") (pinfunction "VDDC_56") (pintype "power_in"))
    )
    (net (code "49") (name "/VREF_A") (class "Default")
      (node (ref "R17") (pin "2") (pinfunction "2_2") (pintype "passive"))
      (node (ref "R18") (pin "1") (pinfunction "1_1") (pintype "passive"))
      (node (ref "U4") (pin "5") (pinfunction "VREF_5") (pintype "power_in"))
    )
    (net (code "50") (name "/VREF_B") (class "Default")
      (node (ref "R21") (pin "2") (pinfunction "2_2") (pintype "passive"))
      (node (ref "R22") (pin "1") (pinfunction "1_1") (pintype "passive"))
      (node (ref "U5") (pin "5") (pinfunction "VREF_5") (pintype "power_in"))
    )
    (net (code "51") (name "/VREF_C") (class "Default")
      (node (ref "R25") (pin "2") (pinfunction "2_2") (pintype "passive"))
      (node (ref "R26") (pin "1") (pinfunction "1_1") (pintype "passive"))
      (node (ref "U6") (pin "5") (pinfunction "VREF_5") (pintype "power_in"))
    )
    (net (code "52") (name "/nFLT_A") (class "Default")
      (node (ref "R15") (pin "1") (pinfunction "1_1") (pintype "passive"))
      (node (ref "U2") (pin "21") (pinfunction "PA4/SSI0RX_21") (pintype "bidirectional"))
      (node (ref "U4") (pin "4") (pinfunction "nFAULT_4") (pintype "input"))
    )
    (net (code "53") (name "/nFLT_B") (class "Default")
      (node (ref "R19") (pin "2") (pinfunction "2_2") (pintype "passive"))
      (node (ref "U2") (pin "23") (pinfunction "PA6_23") (pintype "bidirectional"))
      (node (ref "U5") (pin "4") (pinfunction "nFAULT_4") (pintype "input"))
    )
    (net (code "54") (name "/nFLT_C") (class "Default")
      (node (ref "R23") (pin "2") (pinfunction "2_2") (pintype "passive"))
      (node (ref "U2") (pin "46") (pinfunction "PB1/USB0VBUS_46") (pintype "bidirectional"))
      (node (ref "U6") (pin "4") (pinfunction "nFAULT_4") (pintype "input"))
    )
    (net (code "55") (name "/nSLEEP_A") (class "Default")
      (node (ref "U2") (pin "20") (pinfunction "PA3/SSI0FSS_20") (pintype "bidirectional"))
      (node (ref "U4") (pin "3") (pinfunction "nSLEEP_3") (pintype "input"))
    )
    (net (code "56") (name "/nSLEEP_B") (class "Default")
      (node (ref "U2") (pin "22") (pinfunction "PA5/SSI0TX_22") (pintype "bidirectional"))
      (node (ref "U5") (pin "3") (pinfunction "nSLEEP_3") (pintype "input"))
    )
    (net (code "57") (name "/nSLEEP_C") (class "Default")
      (node (ref "U2") (pin "45") (pinfunction "PB0/USB0ID_45") (pintype "bidirectional"))
      (node (ref "U6") (pin "3") (pinfunction "nSLEEP_3") (pintype "input"))
    )
    (net (code "58") (name "GND") (class "Default")
      (node (ref "C1") (pin "2") (pinfunction "2_2") (pintype "passive"))
      (node (ref "C10") (pin "2") (pinfunction "2_2") (pintype "passive"))
      (node (ref "C11") (pin "2") (pinfunction "2_2") (pintype "passive"))
      (node (ref "C12") (pin "2") (pinfunction "2_2") (pintype "passive"))
      (node (ref "C13") (pin "1") (pinfunction "1_1") (pintype "passive"))
      (node (ref "C14") (pin "1") (pinfunction "1_1") (pintype "passive"))
      (node (ref "C15") (pin "1") (pinfunction "1_1") (pintype "passive"))
      (node (ref "C16") (pin "1") (pinfunction "1_1") (pintype "passive"))
      (node (ref "C17") (pin "1") (pinfunction "1_1") (pintype "passive"))
      (node (ref "C18") (pin "1") (pinfunction "1_1") (pintype "passive"))
      (node (ref "C19") (pin "1") (pinfunction "1_1") (pintype "passive"))
      (node (ref "C2") (pin "1") (pinfunction "1_1") (pintype "passive"))
      (node (ref "C20") (pin "1") (pinfunction "1_1") (pintype "passive"))
      (node (ref "C21") (pin "1") (pinfunction "1_1") (pintype "passive"))
      (node (ref "C22") (pin "1") (pinfunction "1_1") (pintype "passive"))
      (node (ref "C23") (pin "1") (pinfunction "1_1") (pintype "passive"))
      (node (ref "C24") (pin "1") (pinfunction "1_1") (pintype "passive"))
      (node (ref "C25") (pin "1") (pinfunction "1_1") (pintype "passive"))
      (node (ref "C26") (pin "1") (pinfunction "1_1") (pintype "passive"))
      (node (ref "C27") (pin "1") (pinfunction "1_1") (pintype "passive"))
      (node (ref "C28") (pin "1") (pinfunction "1_1") (pintype "passive"))
      (node (ref "C29") (pin "1") (pinfunction "1_1") (pintype "passive"))
      (node (ref "C3") (pin "1") (pinfunction "1_1") (pintype "passive"))
      (node (ref "C32") (pin "1") (pinfunction "1_1") (pintype "passive"))
      (node (ref "C33") (pin "1") (pinfunction "1_1") (pintype "passive"))
      (node (ref "C36") (pin "1") (pinfunction "1_1") (pintype "passive"))
      (node (ref "C37") (pin "1") (pinfunction "1_1") (pintype "passive"))
      (node (ref "C4") (pin "1") (pinfunction "1_1") (pintype "passive"))
      (node (ref "C40") (pin "1") (pinfunction "1_1") (pintype "passive"))
      (node (ref "C41") (pin "1") (pinfunction "1_1") (pintype "passive"))
      (node (ref "C5") (pin "1") (pinfunction "1_1") (pintype "passive"))
      (node (ref "C6") (pin "1") (pinfunction "1_1") (pintype "passive"))
      (node (ref "C7") (pin "2") (pinfunction "2_2") (pintype "passive"))
      (node (ref "C8") (pin "2") (pinfunction "2_2") (pintype "passive"))
      (node (ref "C9") (pin "1") (pinfunction "1_1") (pintype "passive"))
      (node (ref "P1") (pin "1") (pinfunction "1_1") (pintype "passive"))
      (node (ref "P5") (pin "6") (pinfunction "GND_6") (pintype "passive"))
      (node (ref "P6") (pin "6") (pinfunction "GND_6") (pintype "passive"))
      (node (ref "P8") (pin "2") (pinfunction "GND_2") (pintype "passive"))
      (node (ref "P9") (pin "3") (pinfunction "GND_3") (pintype "passive"))
      (node (ref "R1") (pin "1") (pinfunction "1_1") (pintype "passive"))
      (node (ref "R16") (pin "2") (pinfunction "2_2") (pintype "passive"))
      (node (ref "R18") (pin "2") (pinfunction "2_2") (pintype "passive"))
      (node (ref "R20") (pin "2") (pinfunction "2_2") (pintype "passive"))
      (node (ref "R22") (pin "2") (pinfunction "2_2") (pintype "passive"))
      (node (ref "R24") (pin "2") (pinfunction "2_2") (pintype "passive"))
      (node (ref "R26") (pin "2") (pinfunction "2_2") (pintype "passive"))
      (node (ref "U1") (pin "2") (pinfunction "GND_2") (pintype "power_in"))
      (node (ref "U1") (pin "4") (pinfunction "GND_4") (pintype "power_in"))
      (node (ref "U2") (pin "12") (pinfunction "GND_12") (pintype "power_in"))
      (node (ref "U2") (pin "27") (pinfunction "GND_27") (pintype "power_in"))
      (node (ref "U2") (pin "3") (pinfunction "GNDA_3") (pintype "power_in"))
      (node (ref "U2") (pin "32") (pinfunction "WAKE_32") (pintype "input"))
      (node (ref "U2") (pin "34") (pinfunction "XOSC0_34") (pintype "input"))
      (node (ref "U2") (pin "35") (pinfunction "GNDX_35") (pintype "power_in"))
      (node (ref "U2") (pin "39") (pinfunction "GND_39") (pintype "power_in"))
      (node (ref "U2") (pin "55") (pinfunction "GND_55") (pintype "power_in"))
      (node (ref "U3") (pin "13") (pinfunction "GND_13") (pintype "passive"))
      (node (ref "U3") (pin "17") (pinfunction "GND_17") (pintype "passive"))
      (node (ref "U3") (pin "3") (pinfunction "GND_3") (pintype "passive"))
      (node (ref "U4") (pin "15") (pinfunction "GND_15") (pintype "passive"))
      (node (ref "U4") (pin "16") (pinfunction "PMODE_16") (pintype "bidirectional"))
      (node (ref "U4") (pin "7") (pinfunction "IMODE_7") (pintype "bidirectional"))
      (node (ref "U4") (pin "9") (pinfunction "PGND_9") (pintype "passive"))
      (node (ref "U5") (pin "15") (pinfunction "GND_15") (pintype "passive"))
      (node (ref "U5") (pin "16") (pinfunction "PMODE_16") (pintype "bidirectional"))
      (node (ref "U5") (pin "7") (pinfunction "IMODE_7") (pintype "bidirectional"))
      (node (ref "U5") (pin "9") (pinfunction "PGND_9") (pintype "passive"))
      (node (ref "U6") (pin "15") (pinfunction "GND_15") (pintype "passive"))
      (node (ref "U6") (pin "16") (pinfunction "PMODE_16") (pintype "bidirectional"))
      (node (ref "U6") (pin "7") (pinfunction "IMODE_7") (pintype "bidirectional"))
      (node (ref "U6") (pin "9") (pinfunction "PGND_9") (pintype "passive"))
      (node (ref "U7") (pin "4") (pinfunction "GND_4") (pintype "power_in"))
      (node (ref "U8") (pin "4") (pinfunction "GND_4") (pintype "power_in"))
      (node (ref "USB1") (pin "4") (pinfunction "GND_4") (pintype "power_in"))
      (node (ref "X1") (pin "2") (pinfunction "CASE_2") (pintype "passive"))
      (node (ref "X1") (pin "4") (pinfunction "CASE_4") (pintype "passive"))
    )
    (net (code "59") (name "Net-(D1-A)") (class "Default")
      (node (ref "D1") (pin "1") (pinfunction "A_1") (pintype "passive"))
      (node (ref "R13") (pin "1") (pinfunction "1_1") (pintype "passive"))
    )
    (net (code "60") (name "Net-(D2-A)") (class "Default")
      (node (ref "D2") (pin "1") (pinfunction "A_1") (pintype "passive"))
      (node (ref "R14") (pin "1") (pinfunction "1_1") (pintype "passive"))
    )
    (net (code "61") (name "Net-(U3-CTS#)") (class "Default")
      (node (ref "R7") (pin "1") (pinfunction "1_1") (pintype "passive"))
      (node (ref "U3") (pin "4") (pinfunction "CTS#_4") (pintype "passive"))
    )
    (net (code "62") (name "Net-(U3-RTS#)") (class "Default")
      (node (ref "R6") (pin "1") (pinfunction "1_1") (pintype "passive"))
      (node (ref "U3") (pin "16") (pinfunction "RTS#_16") (pintype "passive"))
    )
    (net (code "63") (name "Net-(U3-USBDM)") (class "Default")
      (node (ref "R8") (pin "2") (pinfunction "2_2") (pintype "passive"))
      (node (ref "U3") (pin "7") (pinfunction "USBDM_7") (pintype "passive"))
    )
    (net (code "64") (name "Net-(U3-USBDP)") (class "Default")
      (node (ref "R9") (pin "2") (pinfunction "2_2") (pintype "passive"))
      (node (ref "U3") (pin "6") (pinfunction "USBDP_6") (pintype "passive"))
    )
    (net (code "65") (name "Net-(U4-CPH)") (class "Default")
      (node (ref "C30") (pin "2") (pinfunction "2_2") (pintype "passive"))
      (node (ref "U4") (pin "13") (pinfunction "CPH_13") (pintype "passive"))
    )
    (net (code "66") (name "Net-(U4-CPL)") (class "Default")
      (node (ref "C30") (pin "1") (pinfunction "1_1") (pintype "passive"))
      (node (ref "U4") (pin "14") (pinfunction "CPL_14") (pintype "passive"))
    )
    (net (code "67") (name "Net-(U4-VCP)") (class "Default")
      (node (ref "C31") (pin "1") (pinfunction "1_1") (pintype "passive"))
      (node (ref "U4") (pin "12") (pinfunction "VCP_12") (pintype "power_in"))
    )
    (net (code "68") (name "Net-(U5-CPH)") (class "Default")
      (node (ref "C34") (pin "2") (pinfunction "2_2") (pintype "passive"))
      (node (ref "U5") (pin "13") (pinfunction "CPH_13") (pintype "passive"))
    )
    (net (code "69") (name "Net-(U5-CPL)") (class "Default")
      (node (ref "C34") (pin "1") (pinfunction "1_1") (pintype "passive"))
      (node (ref "U5") (pin "14") (pinfunction "CPL_14") (pintype "passive"))
    )
    (net (code "70") (name "Net-(U5-VCP)") (class "Default")
      (node (ref "C35") (pin "1") (pinfunction "1_1") (pintype "passive"))
      (node (ref "U5") (pin "12") (pinfunction "VCP_12") (pintype "power_in"))
    )
    (net (code "71") (name "Net-(U6-CPH)") (class "Default")
      (node (ref "C38") (pin "2") (pinfunction "2_2") (pintype "passive"))
      (node (ref "U6") (pin "13") (pinfunction "CPH_13") (pintype "passive"))
    )
    (net (code "72") (name "Net-(U6-CPL)") (class "Default")
      (node (ref "C38") (pin "1") (pinfunction "1_1") (pintype "passive"))
      (node (ref "U6") (pin "14") (pinfunction "CPL_14") (pintype "passive"))
    )
    (net (code "73") (name "Net-(U6-VCP)") (class "Default")
      (node (ref "C39") (pin "1") (pinfunction "1_1") (pintype "passive"))
      (node (ref "U6") (pin "12") (pinfunction "VCP_12") (pintype "power_in"))
    )
    (net (code "74") (name "VBUS") (class "Default")
      (node (ref "C1") (pin "1") (pinfunction "1_1") (pintype "passive"))
      (node (ref "C3") (pin "2") (pinfunction "2_2") (pintype "passive"))
      (node (ref "L1") (pin "1") (pinfunction "1_1") (pintype "passive"))
      (node (ref "USB1") (pin "1") (pinfunction "VDD_1") (pintype "power_in"))
    )
    (net (code "75") (name "unconnected-(U2-HIB-Pad33)") (class "Default")
      (node (ref "U2") (pin "33") (pinfunction "HIB_33") (pintype "output+no_connect"))
    )
    (net (code "76") (name "unconnected-(U2-PA7-Pad24)") (class "Default")
      (node (ref "U2") (pin "24") (pinfunction "PA7_24") (pintype "bidirectional"))
    )
    (net (code "77") (name "unconnected-(U2-PB4-Pad58)") (class "Default")
      (node (ref "U2") (pin "58") (pinfunction "PB4_58") (pintype "bidirectional"))
    )
    (net (code "78") (name "unconnected-(U2-PB5-Pad57)") (class "Default")
      (node (ref "U2") (pin "57") (pinfunction "PB5_57") (pintype "bidirectional"))
    )
    (net (code "79") (name "unconnected-(U2-PD1-Pad62)") (class "Default")
      (node (ref "U2") (pin "62") (pinfunction "PD1_62") (pintype "bidirectional"))
    )
    (net (code "80") (name "unconnected-(U2-PD2-Pad63)") (class "Default")
      (node (ref "U2") (pin "63") (pinfunction "PD2_63") (pintype "bidirectional"))
    )
    (net (code "81") (name "unconnected-(U2-PD3-Pad64)") (class "Default")
      (node (ref "U2") (pin "64") (pinfunction "PD3_64") (pintype "bidirectional"))
    )
    (net (code "82") (name "unconnected-(U2-PD4-Pad43)") (class "Default")
      (node (ref "U2") (pin "43") (pinfunction "PD4_43") (pintype "bidirectional"))
    )
    (net (code "83") (name "unconnected-(U2-PD5-Pad44)") (class "Default")
      (node (ref "U2") (pin "44") (pinfunction "PD5_44") (pintype "bidirectional"))
    )
    (net (code "84") (name "unconnected-(U2-PD6-Pad53)") (class "Default")
      (node (ref "U2") (pin "53") (pinfunction "PD6_53") (pintype "bidirectional"))
    )
    (net (code "85") (name "unconnected-(U2-PE0-Pad9)") (class "Default")
      (node (ref "U2") (pin "9") (pinfunction "PE0_9") (pintype "bidirectional"))
    )
    (net (code "86") (name "unconnected-(U2-PE4-Pad59)") (class "Default")
      (node (ref "U2") (pin "59") (pinfunction "PE4_59") (pintype "bidirectional"))
    )
    (net (code "87") (name "unconnected-(U2-PE5-Pad60)") (class "Default")
      (node (ref "U2") (pin "60") (pinfunction "PE5_60") (pintype "bidirectional"))
    )
    (net (code "88") (name "unconnected-(U2-PF0-Pad28)") (class "Default")
      (node (ref "U2") (pin "28") (pinfunction "PF0_28") (pintype "bidirectional"))
    )
    (net (code "89") (name "unconnected-(U2-PF1-Pad29)") (class "Default")
      (node (ref "U2") (pin "29") (pinfunction "PF1_29") (pintype "bidirectional"))
    )
    (net (code "90") (name "unconnected-(U2-PF2-Pad30)") (class "Default")
      (node (ref "U2") (pin "30") (pinfunction "PF2_30") (pintype "bidirectional"))
    )
    (net (code "91") (name "unconnected-(U2-PF3-Pad31)") (class "Default")
      (node (ref "U2") (pin "31") (pinfunction "PF3_31") (pintype "bidirectional"))
    )
    (net (code "92") (name "unconnected-(U2-XOSC1-Pad36)") (class "Default")
      (node (ref "U2") (pin "36") (pinfunction "XOSC1_36") (pintype "output+no_connect"))
    )
    (net (code "93") (name "unconnected-(U3-CBUS0-Pad12)") (class "Default")
      (node (ref "U3") (pin "12") (pinfunction "CBUS0_12") (pintype "passive+no_connect"))
    )
    (net (code "94") (name "unconnected-(U3-CBUS3-Pad14)") (class "Default")
      (node (ref "U3") (pin "14") (pinfunction "CBUS3_14") (pintype "passive+no_connect"))
    )
  )
)
